# pmic_tps65263_buck.net
KiCad netlist of a schematic drawn in Altium Designer
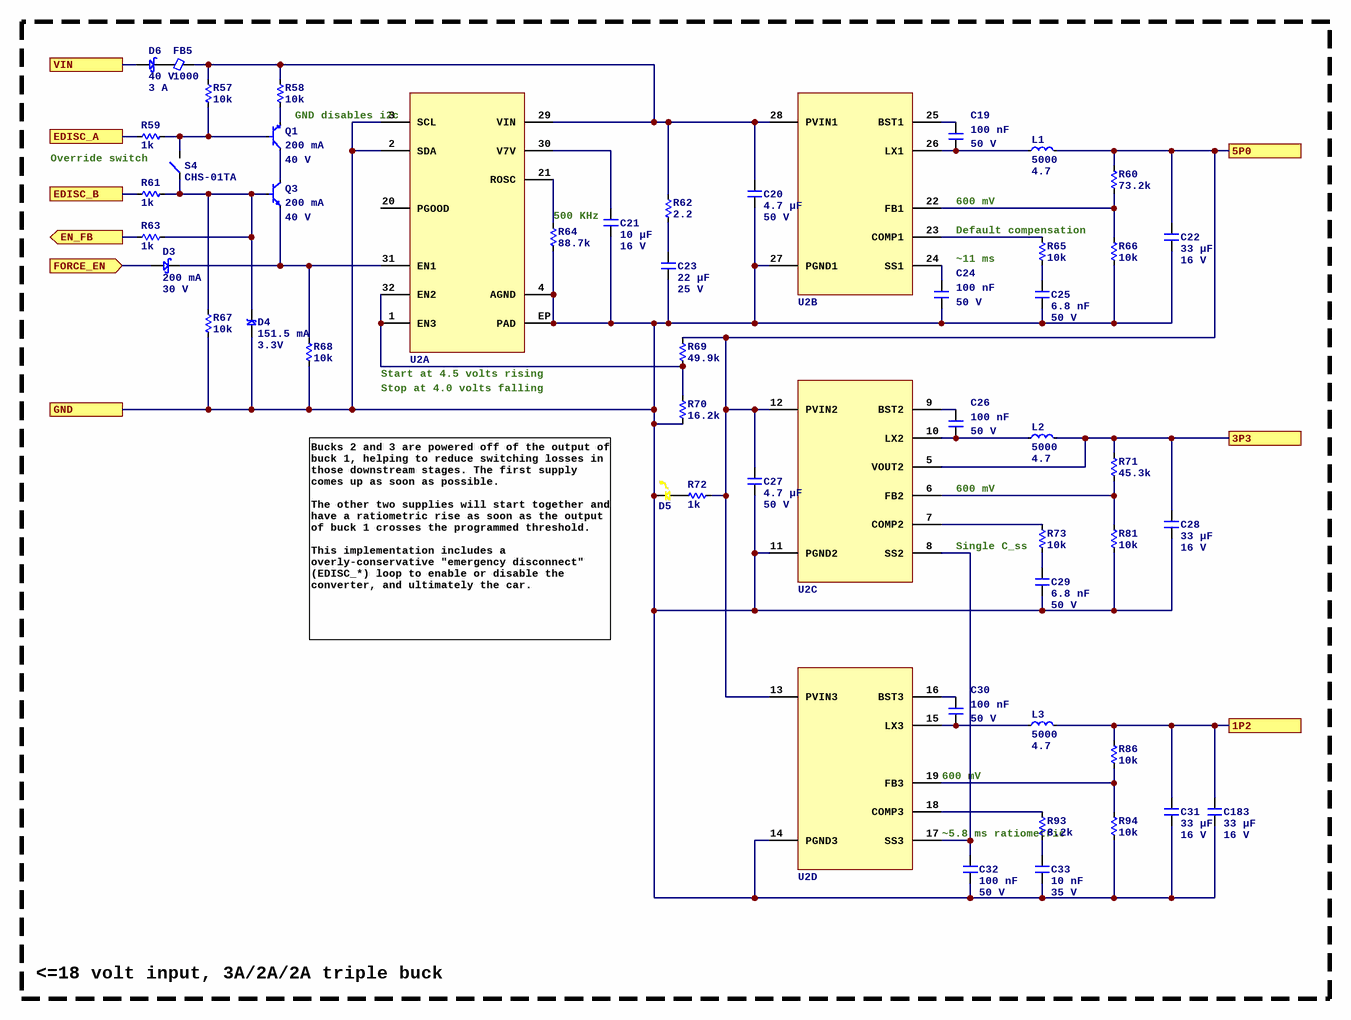
[diagram p0: pmic_tps65263_buck.SchDoc]

(export (version "E")
  (design (tool "Eeschema 10.0.6"))
  (components
    (comp (ref "C19")
      (value "CL05B104KB54PNC")
      (footprint "C0402")
      (fields
        (field (name "CAPACITANCE") "100 nF")
        (field (name "MANUFACTURER") "Samsung Electro-Mechanics")
        (field (name "VOLTAGE RATING") "50 V")
      )
      (libsource (lib "database") (part "__template_cap"))
    )
    (comp (ref "C20")
      (value "0805B475K500NT")
      (footprint "C0805")
      (fields
        (field (name "CAPACITANCE") "4.7 µF")
        (field (name "MANUFACTURER") "FH (Guangdong Fenghua Advanced Tech)")
        (field (name "VOLTAGE RATING") "50 V")
      )
      (libsource (lib "database") (part "__template_cap"))
    )
    (comp (ref "C21")
      (value "CL21B106KOQNNNE")
      (footprint "C0805")
      (fields
        (field (name "CAPACITANCE") "10 µF")
        (field (name "MANUFACTURER") "Samsung Electro-Mechanics")
        (field (name "VOLTAGE RATING") "16 V")
      )
      (libsource (lib "database") (part "__template_cap"))
    )
    (comp (ref "C22")
      (value "C4532X7R1C336MT000N")
      (footprint "C1812")
      (fields
        (field (name "CAPACITANCE") "33 µF")
        (field (name "MANUFACTURER") "TDK")
        (field (name "VOLTAGE RATING") "16 V")
      )
      (libsource (lib "database") (part "__template_cap"))
    )
    (comp (ref "C23")
      (value "C5750X7R1E226MT000N")
      (footprint "C2220")
      (fields
        (field (name "CAPACITANCE") "22 µF")
        (field (name "MANUFACTURER") "TDK")
        (field (name "VOLTAGE RATING") "25 V")
      )
      (libsource (lib "database") (part "__template_cap"))
    )
    (comp (ref "C24")
      (value "CL05B104KB54PNC")
      (footprint "C0402")
      (fields
        (field (name "CAPACITANCE") "100 nF")
        (field (name "MANUFACTURER") "Samsung Electro-Mechanics")
        (field (name "VOLTAGE RATING") "50 V")
      )
      (libsource (lib "database") (part "__template_cap"))
    )
    (comp (ref "C25")
      (value "GRM1555C1H682GE01D")
      (footprint "C0402")
      (fields
        (field (name "CAPACITANCE") "6.8 nF")
        (field (name "MANUFACTURER") "Murata Electronics")
        (field (name "VOLTAGE RATING") "50 V")
      )
      (libsource (lib "database") (part "__template_cap"))
    )
    (comp (ref "C26")
      (value "CL05B104KB54PNC")
      (footprint "C0402")
      (fields
        (field (name "CAPACITANCE") "100 nF")
        (field (name "MANUFACTURER") "Samsung Electro-Mechanics")
        (field (name "VOLTAGE RATING") "50 V")
      )
      (libsource (lib "database") (part "__template_cap"))
    )
    (comp (ref "C27")
      (value "0805B475K500NT")
      (footprint "C0805")
      (fields
        (field (name "CAPACITANCE") "4.7 µF")
        (field (name "MANUFACTURER") "FH (Guangdong Fenghua Advanced Tech)")
        (field (name "VOLTAGE RATING") "50 V")
      )
      (libsource (lib "database") (part "__template_cap"))
    )
    (comp (ref "C28")
      (value "C4532X7R1C336MT000N")
      (footprint "C1812")
      (fields
        (field (name "CAPACITANCE") "33 µF")
        (field (name "MANUFACTURER") "TDK")
        (field (name "VOLTAGE RATING") "16 V")
      )
      (libsource (lib "database") (part "__template_cap"))
    )
    (comp (ref "C29")
      (value "GRM1555C1H682GE01D")
      (footprint "C0402")
      (fields
        (field (name "CAPACITANCE") "6.8 nF")
        (field (name "MANUFACTURER") "Murata Electronics")
        (field (name "VOLTAGE RATING") "50 V")
      )
      (libsource (lib "database") (part "__template_cap"))
    )
    (comp (ref "C30")
      (value "CL05B104KB54PNC")
      (footprint "C0402")
      (fields
        (field (name "CAPACITANCE") "100 nF")
        (field (name "MANUFACTURER") "Samsung Electro-Mechanics")
        (field (name "VOLTAGE RATING") "50 V")
      )
      (libsource (lib "database") (part "__template_cap"))
    )
    (comp (ref "C31")
      (value "C4532X7R1C336MT000N")
      (footprint "C1812")
      (fields
        (field (name "CAPACITANCE") "33 µF")
        (field (name "MANUFACTURER") "TDK")
        (field (name "VOLTAGE RATING") "16 V")
      )
      (libsource (lib "database") (part "__template_cap"))
    )
    (comp (ref "C32")
      (value "CL05B104KB54PNC")
      (footprint "C0402")
      (fields
        (field (name "CAPACITANCE") "100 nF")
        (field (name "MANUFACTURER") "Samsung Electro-Mechanics")
        (field (name "VOLTAGE RATING") "50 V")
      )
      (libsource (lib "database") (part "__template_cap"))
    )
    (comp (ref "C33")
      (value "GRM1555CYA103GE01D")
      (footprint "C0402")
      (fields
        (field (name "CAPACITANCE") "10 nF")
        (field (name "MANUFACTURER") "Murata Electronics")
        (field (name "VOLTAGE RATING") "35 V")
      )
      (libsource (lib "database") (part "__template_cap"))
    )
    (comp (ref "C183")
      (value "C4532X7R1C336MT000N")
      (footprint "C1812")
      (fields
        (field (name "CAPACITANCE") "33 µF")
        (field (name "MANUFACTURER") "TDK")
        (field (name "VOLTAGE RATING") "16 V")
      )
      (libsource (lib "database") (part "__template_cap"))
    )
    (comp (ref "D3")
      (value "BAT54XV2T1G")
      (footprint "SOD523")
      (description "ON Semi BAT54XV2T1G; SMT Schottky Diode; 30V 200mA; 5ns; 2-Pin SOD-523")
      (fields
        (field (name "MANUFACTURER") "onsemi")
        (field (name "CURRENT") "200 mA")
        (field (name "VR") "30 V")
      )
      (libsource (lib "database") (part "__template_diode_schottky"))
    )
    (comp (ref "D4")
      (value "SZMM5Z3V3T1G")
      (footprint "SOD523")
      (description "500 mW Standard Tolerance Zener Diode Voltage Regulators 3.3 V (Automotive)")
      (fields
        (field (name "MANUFACTURER") "onsemi")
        (field (name "CURRENT") "151.5 mA")
        (field (name "VR") "3.3V")
      )
      (libsource (lib "database") (part "__template_diode_zener"))
    )
    (comp (ref "D5")
      (value "LTST-C190YKT")
      (footprint "LED_0603P_YELLOW")
      (description "LED YELLOW CLEAR 0603 SMD")
      (fields (field (name "MANUFACTURER") "Lite-On Inc"))
      (libsource (lib "database") (part "__template_led_yellow"))
    )
    (comp (ref "D6")
      (value "B340A-13-F")
      (footprint "SMA")
      (description "Rectifier Diode, Schottky, 1 Phase, 1 Element, 3A, 40V V(RRM), Silicon")
      (fields
        (field (name "MANUFACTURER") "Diodes")
        (field (name "VR") "40 V")
        (field (name "CURRENT") "3 A")
      )
      (libsource (lib "database") (part "__template_diode_schottky"))
    )
    (comp (ref "FB5")
      (value "HCB2012KF-102T10")
      (footprint "FB0805")
      (fields (field (name "MANUFACTURER") "TAI-TECH") (field (name "CURRENT RATING (MA)") "1000"))
      (libsource (lib "database") (part "__template_fb"))
    )
    (comp (ref "L1")
      (value "FTC404020S4R7MGCA")
      (footprint "SMD-4.1x4.1x2.0")
      (description "4.7 µH SMD power inductor")
      (fields
        (field (name "MANUFACTURER") "cjiang")
        (field (name "CURRENT RATING (MA)") "5000")
        (field (name "INDUCTANCE (ΜH)") "4.7")
      )
      (libsource (lib "database") (part "__template_inductor"))
    )
    (comp (ref "L2")
      (value "FTC404020S4R7MGCA")
      (footprint "SMD-4.1x4.1x2.0")
      (description "4.7 µH SMD power inductor")
      (fields
        (field (name "MANUFACTURER") "cjiang")
        (field (name "CURRENT RATING (MA)") "5000")
        (field (name "INDUCTANCE (ΜH)") "4.7")
      )
      (libsource (lib "database") (part "__template_inductor"))
    )
    (comp (ref "L3")
      (value "FTC404020S4R7MGCA")
      (footprint "SMD-4.1x4.1x2.0")
      (description "4.7 µH SMD power inductor")
      (fields
        (field (name "MANUFACTURER") "cjiang")
        (field (name "CURRENT RATING (MA)") "5000")
        (field (name "INDUCTANCE (ΜH)") "4.7")
      )
      (libsource (lib "database") (part "__template_inductor"))
    )
    (comp (ref "Q1")
      (value "MMBT3906T")
      (footprint "3SOT523")
      (description "Bipolar (BJT) Transistor NPN 40 V 200 mA 300MHz 150 mW Surface Mount SOT-523")
      (fields
        (field (name "MANUFACTURER") "Shenzhen Slkormicro Semicon Co., Ltd.")
        (field (name "CURRENT") "200 mA")
        (field (name "VOLTAGE") "40 V")
      )
      (libsource (lib "database") (part "MMBT3906T"))
    )
    (comp (ref "Q3")
      (value "MMBT3904T")
      (footprint "3SOT523")
      (description "Bipolar (BJT) Transistor NPN 40 V 200 mA 300MHz 150 mW Surface Mount SOT-523")
      (fields
        (field (name "MANUFACTURER") "Shenzhen Slkormicro Semicon Co., Ltd.")
        (field (name "CURRENT") "200 mA")
        (field (name "VOLTAGE") "40 V")
      )
      (libsource (lib "database") (part "MMBT3904T"))
    )
    (comp (ref "R57")
      (value "10k")
      (footprint "R0402")
      (fields
        (field (name "TOLERANCE") "1%")
        (field (name "MANUFACTURER PART NUMBER") "0402WGF1002TCE")
        (field (name "MANUFACTURER") "UNI-ROYAL(Uniroyal Elec)")
      )
      (libsource (lib "database") (part "__template_resistor"))
    )
    (comp (ref "R58")
      (value "10k")
      (footprint "R0402")
      (fields
        (field (name "TOLERANCE") "1%")
        (field (name "MANUFACTURER PART NUMBER") "0402WGF1002TCE")
        (field (name "MANUFACTURER") "UNI-ROYAL(Uniroyal Elec)")
      )
      (libsource (lib "database") (part "__template_resistor"))
    )
    (comp (ref "R59")
      (value "1k")
      (footprint "R0402")
      (fields
        (field (name "TOLERANCE") "1%")
        (field (name "MANUFACTURER PART NUMBER") "0402WGF1001TCE")
        (field (name "MANUFACTURER") "UNI-ROYAL(Uniroyal Elec)")
      )
      (libsource (lib "database") (part "__template_resistor"))
    )
    (comp (ref "R60")
      (value "73.2k")
      (footprint "R0402")
      (fields
        (field (name "TOLERANCE") "1%")
        (field (name "MANUFACTURER PART NUMBER") "0402WGF7322TCE")
        (field (name "MANUFACTURER") "UNI-ROYAL(Uniroyal Elec)")
      )
      (libsource (lib "database") (part "__template_resistor"))
    )
    (comp (ref "R61")
      (value "1k")
      (footprint "R0402")
      (fields
        (field (name "TOLERANCE") "1%")
        (field (name "MANUFACTURER PART NUMBER") "0402WGF1001TCE")
        (field (name "MANUFACTURER") "UNI-ROYAL(Uniroyal Elec)")
      )
      (libsource (lib "database") (part "__template_resistor"))
    )
    (comp (ref "R62")
      (value "2.2")
      (footprint "R0805")
      (fields
        (field (name "TOLERANCE") "1%")
        (field (name "MANUFACTURER PART NUMBER") "HP05W3F220KT5E")
        (field (name "MANUFACTURER") "UNI-ROYAL(Uniroyal Elec)")
      )
      (libsource (lib "database") (part "__template_resistor"))
    )
    (comp (ref "R63")
      (value "1k")
      (footprint "R0402")
      (fields
        (field (name "TOLERANCE") "1%")
        (field (name "MANUFACTURER PART NUMBER") "0402WGF1001TCE")
        (field (name "MANUFACTURER") "UNI-ROYAL(Uniroyal Elec)")
      )
      (libsource (lib "database") (part "__template_resistor"))
    )
    (comp (ref "R64")
      (value "88.7k")
      (footprint "R0402")
      (fields
        (field (name "TOLERANCE") "1%")
        (field (name "MANUFACTURER PART NUMBER") "0402WGF8872TCE")
        (field (name "MANUFACTURER") "UNI-ROYAL(Uniroyal Elec)")
      )
      (libsource (lib "database") (part "__template_resistor"))
    )
    (comp (ref "R65")
      (value "10k")
      (footprint "R0402")
      (fields
        (field (name "TOLERANCE") "1%")
        (field (name "MANUFACTURER PART NUMBER") "0402WGF1002TCE")
        (field (name "MANUFACTURER") "UNI-ROYAL(Uniroyal Elec)")
      )
      (libsource (lib "database") (part "__template_resistor"))
    )
    (comp (ref "R66")
      (value "10k")
      (footprint "R0402")
      (fields
        (field (name "TOLERANCE") "1%")
        (field (name "MANUFACTURER PART NUMBER") "0402WGF1002TCE")
        (field (name "MANUFACTURER") "UNI-ROYAL(Uniroyal Elec)")
      )
      (libsource (lib "database") (part "__template_resistor"))
    )
    (comp (ref "R67")
      (value "10k")
      (footprint "R0402")
      (fields
        (field (name "TOLERANCE") "1%")
        (field (name "MANUFACTURER PART NUMBER") "0402WGF1002TCE")
        (field (name "MANUFACTURER") "UNI-ROYAL(Uniroyal Elec)")
      )
      (libsource (lib "database") (part "__template_resistor"))
    )
    (comp (ref "R68")
      (value "10k")
      (footprint "R0402")
      (fields
        (field (name "TOLERANCE") "1%")
        (field (name "MANUFACTURER PART NUMBER") "0402WGF1002TCE")
        (field (name "MANUFACTURER") "UNI-ROYAL(Uniroyal Elec)")
      )
      (libsource (lib "database") (part "__template_resistor"))
    )
    (comp (ref "R69")
      (value "49.9k")
      (footprint "R0402")
      (fields
        (field (name "TOLERANCE") "0.5%")
        (field (name "MANUFACTURER PART NUMBER") "0402WGD4992TCE")
        (field (name "MANUFACTURER") "UNI-ROYAL(Uniroyal Elec)")
      )
      (libsource (lib "database") (part "__template_resistor"))
    )
    (comp (ref "R70")
      (value "16.2k")
      (footprint "R0402")
      (fields
        (field (name "TOLERANCE") "1%")
        (field (name "MANUFACTURER PART NUMBER") "0402WGF1622TCE")
        (field (name "MANUFACTURER") "UNI-ROYAL(Uniroyal Elec)")
      )
      (libsource (lib "database") (part "__template_resistor"))
    )
    (comp (ref "R71")
      (value "45.3k")
      (footprint "R0402")
      (fields
        (field (name "TOLERANCE") "1%")
        (field (name "MANUFACTURER PART NUMBER") "FRC0402F4532TS")
        (field (name "MANUFACTURER") "FOJAN")
      )
      (libsource (lib "database") (part "__template_resistor"))
    )
    (comp (ref "R72")
      (value "1k")
      (footprint "R0402")
      (fields
        (field (name "TOLERANCE") "1%")
        (field (name "MANUFACTURER PART NUMBER") "0402WGF1001TCE")
        (field (name "MANUFACTURER") "UNI-ROYAL(Uniroyal Elec)")
      )
      (libsource (lib "database") (part "__template_resistor"))
    )
    (comp (ref "R73")
      (value "10k")
      (footprint "R0402")
      (fields
        (field (name "TOLERANCE") "1%")
        (field (name "MANUFACTURER PART NUMBER") "0402WGF1002TCE")
        (field (name "MANUFACTURER") "UNI-ROYAL(Uniroyal Elec)")
      )
      (libsource (lib "database") (part "__template_resistor"))
    )
    (comp (ref "R81")
      (value "10k")
      (footprint "R0402")
      (fields
        (field (name "TOLERANCE") "1%")
        (field (name "MANUFACTURER PART NUMBER") "0402WGF1002TCE")
        (field (name "MANUFACTURER") "UNI-ROYAL(Uniroyal Elec)")
      )
      (libsource (lib "database") (part "__template_resistor"))
    )
    (comp (ref "R86")
      (value "10k")
      (footprint "R0402")
      (fields
        (field (name "TOLERANCE") "1%")
        (field (name "MANUFACTURER PART NUMBER") "0402WGF1002TCE")
        (field (name "MANUFACTURER") "UNI-ROYAL(Uniroyal Elec)")
      )
      (libsource (lib "database") (part "__template_resistor"))
    )
    (comp (ref "R93")
      (value "8.2k")
      (footprint "R0402")
      (fields
        (field (name "TOLERANCE") "1%")
        (field (name "MANUFACTURER PART NUMBER") "0402WGF8201TCE")
        (field (name "MANUFACTURER") "UNI-ROYAL(Uniroyal Elec)")
      )
      (libsource (lib "database") (part "__template_resistor"))
    )
    (comp (ref "R94")
      (value "10k")
      (footprint "R0402")
      (fields
        (field (name "TOLERANCE") "1%")
        (field (name "MANUFACTURER PART NUMBER") "0402WGF1002TCE")
        (field (name "MANUFACTURER") "UNI-ROYAL(Uniroyal Elec)")
      )
      (libsource (lib "database") (part "__template_resistor"))
    )
    (comp (ref "S4")
      (value "CHS-01TA")
      (footprint "SWITCH_NIDEC_CHS-01TA")
      (description "DIP Switch, Slide, SPST, Flush, Recessed, 6VDC, 100mA, CHS Series Ž Nidec Components CHS-01TA")
      (fields (field (name "MANUFACTURER") "Nidec Copal"))
      (libsource (lib "database") (part "CHS-01TA"))
    )
    (comp (ref "U2")
      (value "TPS65263QRHBRQ1")
      (footprint "TI_RHB")
      (description "Switching Regulator, Current-mode, 3A, 2300kHz Switching Freq-Max, PQCC32")
      (fields (field (name "MANUFACTURER") "Texas Instruments"))
      (libsource (lib "database") (part "TPS65263QRHBRQ1"))
    )
  )
  (nets
    (net (code "1") (name "/1P2") (class "Default")
      (node (ref "C183") (pin "1") (pintype "passive"))
      (node (ref "C31") (pin "1") (pintype "passive"))
      (node (ref "L3") (pin "2") (pintype "passive"))
      (node (ref "R86") (pin "2") (pintype "passive"))
    )
    (net (code "2") (name "/3P3") (class "Default")
      (node (ref "C28") (pin "1") (pintype "passive"))
      (node (ref "L2") (pin "2") (pintype "passive"))
      (node (ref "R71") (pin "2") (pintype "passive"))
      (node (ref "U2") (pin "5") (pinfunction "VOUT2_5") (pintype "passive"))
    )
    (net (code "3") (name "/5P0") (class "Default")
      (node (ref "C22") (pin "1") (pintype "passive"))
      (node (ref "C27") (pin "1") (pintype "passive"))
      (node (ref "L1") (pin "2") (pintype "passive"))
      (node (ref "R60") (pin "2") (pintype "passive"))
      (node (ref "R69") (pin "2") (pintype "passive"))
      (node (ref "R72") (pin "2") (pintype "passive"))
      (node (ref "U2") (pin "12") (pinfunction "PVIN2_12") (pintype "passive"))
      (node (ref "U2") (pin "13") (pinfunction "PVIN3_13") (pintype "passive"))
    )
    (net (code "4") (name "/EDISC_A") (class "Default") (node (ref "R59") (pin "1") (pintype "passive")))
    (net (code "5") (name "/EDISC_B") (class "Default") (node (ref "R61") (pin "1") (pintype "passive")))
    (net (code "6") (name "/EN_FB") (class "Default") (node (ref "R63") (pin "1") (pintype "passive")))
    (net (code "7") (name "/FORCE_EN") (class "Default") (node (ref "D3") (pin "1") (pintype "passive")))
    (net (code "8") (name "/GND") (class "Default")
      (node (ref "C183") (pin "2") (pintype "passive"))
      (node (ref "C20") (pin "2") (pintype "passive"))
      (node (ref "C21") (pin "2") (pintype "passive"))
      (node (ref "C22") (pin "2") (pintype "passive"))
      (node (ref "C23") (pin "2") (pintype "passive"))
      (node (ref "C24") (pin "2") (pintype "passive"))
      (node (ref "C25") (pin "2") (pintype "passive"))
      (node (ref "C27") (pin "2") (pintype "passive"))
      (node (ref "C28") (pin "2") (pintype "passive"))
      (node (ref "C29") (pin "2") (pintype "passive"))
      (node (ref "C31") (pin "2") (pintype "passive"))
      (node (ref "C32") (pin "2") (pintype "passive"))
      (node (ref "C33") (pin "2") (pintype "passive"))
      (node (ref "D4") (pin "1") (pintype "passive"))
      (node (ref "D5") (pin "2") (pintype "passive"))
      (node (ref "R64") (pin "1") (pintype "passive"))
      (node (ref "R66") (pin "1") (pintype "passive"))
      (node (ref "R67") (pin "1") (pintype "passive"))
      (node (ref "R68") (pin "1") (pintype "passive"))
      (node (ref "R70") (pin "1") (pintype "passive"))
      (node (ref "R81") (pin "1") (pintype "passive"))
      (node (ref "R94") (pin "1") (pintype "passive"))
      (node (ref "U2") (pin "11") (pinfunction "PGND2_11") (pintype "passive"))
      (node (ref "U2") (pin "14") (pinfunction "PGND3_14") (pintype "passive"))
      (node (ref "U2") (pin "2") (pinfunction "SDA_2") (pintype "passive"))
      (node (ref "U2") (pin "27") (pinfunction "PGND1_27") (pintype "passive"))
      (node (ref "U2") (pin "3") (pinfunction "SCL_3") (pintype "passive"))
      (node (ref "U2") (pin "4") (pinfunction "AGND_4") (pintype "passive"))
      (node (ref "U2") (pin "EP") (pinfunction "PAD_EP") (pintype "passive"))
    )
    (net (code "9") (name "/VIN") (class "Default") (node (ref "D6") (pin "1") (pintype "passive")))
    (net (code "10") (name "Net-(C23-Pad1)") (class "Default")
      (node (ref "C23") (pin "1") (pintype "passive"))
      (node (ref "R62") (pin "1") (pintype "passive"))
    )
    (net (code "11") (name "Net-(C25-Pad1)") (class "Default")
      (node (ref "C25") (pin "1") (pintype "passive"))
      (node (ref "R65") (pin "1") (pintype "passive"))
    )
    (net (code "12") (name "Net-(C29-Pad1)") (class "Default")
      (node (ref "C29") (pin "1") (pintype "passive"))
      (node (ref "R73") (pin "1") (pintype "passive"))
    )
    (net (code "13") (name "Net-(C33-Pad1)") (class "Default")
      (node (ref "C33") (pin "1") (pintype "passive"))
      (node (ref "R93") (pin "1") (pintype "passive"))
    )
    (net (code "14") (name "Net-(D5-Pad1)") (class "Default")
      (node (ref "D5") (pin "1") (pintype "passive"))
      (node (ref "R72") (pin "1") (pintype "passive"))
    )
    (net (code "15") (name "Net-(D6-Pad2)") (class "Default")
      (node (ref "D6") (pin "2") (pintype "passive"))
      (node (ref "FB5") (pin "1") (pintype "passive"))
    )
    (net (code "16") (name "Net-(Q1-B)") (class "Default")
      (node (ref "Q1") (pin "1") (pinfunction "B_1") (pintype "passive"))
      (node (ref "R57") (pin "1") (pintype "passive"))
      (node (ref "R59") (pin "2") (pintype "passive"))
      (node (ref "S4") (pin "2") (pintype "passive"))
    )
    (net (code "17") (name "Net-(Q1-C)") (class "Default")
      (node (ref "Q1") (pin "3") (pinfunction "C_3") (pintype "passive"))
      (node (ref "Q3") (pin "3") (pinfunction "C_3") (pintype "passive"))
    )
    (net (code "18") (name "Net-(Q1-E)") (class "Default")
      (node (ref "Q1") (pin "2") (pinfunction "E_2") (pintype "passive"))
      (node (ref "R58") (pin "1") (pintype "passive"))
    )
    (net (code "19") (name "Net-(Q3-B)") (class "Default")
      (node (ref "D4") (pin "2") (pintype "passive"))
      (node (ref "Q3") (pin "1") (pinfunction "B_1") (pintype "passive"))
      (node (ref "R61") (pin "2") (pintype "passive"))
      (node (ref "R63") (pin "2") (pintype "passive"))
      (node (ref "R67") (pin "2") (pintype "passive"))
      (node (ref "S4") (pin "1") (pintype "passive"))
    )
    (net (code "20") (name "Net-(Q3-E)") (class "Default")
      (node (ref "D3") (pin "2") (pintype "passive"))
      (node (ref "Q3") (pin "2") (pinfunction "E_2") (pintype "passive"))
      (node (ref "R68") (pin "2") (pintype "passive"))
      (node (ref "U2") (pin "31") (pinfunction "EN1_31") (pintype "passive"))
    )
    (net (code "21") (name "Net-(U2A-EN2)") (class "Default")
      (node (ref "R69") (pin "1") (pintype "passive"))
      (node (ref "R70") (pin "2") (pintype "passive"))
      (node (ref "U2") (pin "1") (pinfunction "EN3_1") (pintype "passive"))
      (node (ref "U2") (pin "32") (pinfunction "EN2_32") (pintype "passive"))
    )
    (net (code "22") (name "Net-(U2A-ROSC)") (class "Default")
      (node (ref "R64") (pin "2") (pintype "passive"))
      (node (ref "U2") (pin "21") (pinfunction "ROSC_21") (pintype "passive"))
    )
    (net (code "23") (name "Net-(U2A-V7V)") (class "Default")
      (node (ref "C21") (pin "1") (pintype "passive"))
      (node (ref "U2") (pin "30") (pinfunction "V7V_30") (pintype "passive"))
    )
    (net (code "24") (name "Net-(U2A-VIN)") (class "Default")
      (node (ref "C20") (pin "1") (pintype "passive"))
      (node (ref "FB5") (pin "2") (pintype "passive"))
      (node (ref "R57") (pin "2") (pintype "passive"))
      (node (ref "R58") (pin "2") (pintype "passive"))
      (node (ref "R62") (pin "2") (pintype "passive"))
      (node (ref "U2") (pin "28") (pinfunction "PVIN1_28") (pintype "passive"))
      (node (ref "U2") (pin "29") (pinfunction "VIN_29") (pintype "passive"))
    )
    (net (code "25") (name "Net-(U2B-BST1)") (class "Default")
      (node (ref "C19") (pin "1") (pintype "passive"))
      (node (ref "U2") (pin "25") (pinfunction "BST1_25") (pintype "passive"))
    )
    (net (code "26") (name "Net-(U2B-COMP1)") (class "Default")
      (node (ref "R65") (pin "2") (pintype "passive"))
      (node (ref "U2") (pin "23") (pinfunction "COMP1_23") (pintype "passive"))
    )
    (net (code "27") (name "Net-(U2B-FB1)") (class "Default")
      (node (ref "R60") (pin "1") (pintype "passive"))
      (node (ref "R66") (pin "2") (pintype "passive"))
      (node (ref "U2") (pin "22") (pinfunction "FB1_22") (pintype "passive"))
    )
    (net (code "28") (name "Net-(U2B-LX1)") (class "Default")
      (node (ref "C19") (pin "2") (pintype "passive"))
      (node (ref "L1") (pin "1") (pintype "passive"))
      (node (ref "U2") (pin "26") (pinfunction "LX1_26") (pintype "passive"))
    )
    (net (code "29") (name "Net-(U2B-SS1)") (class "Default")
      (node (ref "C24") (pin "1") (pintype "passive"))
      (node (ref "U2") (pin "24") (pinfunction "SS1_24") (pintype "passive"))
    )
    (net (code "30") (name "Net-(U2C-BST2)") (class "Default")
      (node (ref "C26") (pin "1") (pintype "passive"))
      (node (ref "U2") (pin "9") (pinfunction "BST2_9") (pintype "passive"))
    )
    (net (code "31") (name "Net-(U2C-COMP2)") (class "Default")
      (node (ref "R73") (pin "2") (pintype "passive"))
      (node (ref "U2") (pin "7") (pinfunction "COMP2_7") (pintype "passive"))
    )
    (net (code "32") (name "Net-(U2C-FB2)") (class "Default")
      (node (ref "R71") (pin "1") (pintype "passive"))
      (node (ref "R81") (pin "2") (pintype "passive"))
      (node (ref "U2") (pin "6") (pinfunction "FB2_6") (pintype "passive"))
    )
    (net (code "33") (name "Net-(U2C-LX2)") (class "Default")
      (node (ref "C26") (pin "2") (pintype "passive"))
      (node (ref "L2") (pin "1") (pintype "passive"))
      (node (ref "U2") (pin "10") (pinfunction "LX2_10") (pintype "passive"))
    )
    (net (code "34") (name "Net-(U2C-SS2)") (class "Default")
      (node (ref "C32") (pin "1") (pintype "passive"))
      (node (ref "U2") (pin "17") (pinfunction "SS3_17") (pintype "passive"))
      (node (ref "U2") (pin "8") (pinfunction "SS2_8") (pintype "passive"))
    )
    (net (code "35") (name "Net-(U2D-BST3)") (class "Default")
      (node (ref "C30") (pin "1") (pintype "passive"))
      (node (ref "U2") (pin "16") (pinfunction "BST3_16") (pintype "passive"))
    )
    (net (code "36") (name "Net-(U2D-COMP3)") (class "Default")
      (node (ref "R93") (pin "2") (pintype "passive"))
      (node (ref "U2") (pin "18") (pinfunction "COMP3_18") (pintype "passive"))
    )
    (net (code "37") (name "Net-(U2D-FB3)") (class "Default")
      (node (ref "R86") (pin "1") (pintype "passive"))
      (node (ref "R94") (pin "2") (pintype "passive"))
      (node (ref "U2") (pin "19") (pinfunction "FB3_19") (pintype "passive"))
    )
    (net (code "38") (name "Net-(U2D-LX3)") (class "Default")
      (node (ref "C30") (pin "2") (pintype "passive"))
      (node (ref "L3") (pin "1") (pintype "passive"))
      (node (ref "U2") (pin "15") (pinfunction "LX3_15") (pintype "passive"))
    )
    (net (code "39") (name "unconnected-(U2A-PGOOD-Pad20)") (class "Default")
      (node (ref "U2") (pin "20") (pinfunction "PGOOD_20") (pintype "passive"))
    )
  )
)
